# hexapod.net
KiCad netlist of a schematic drawn in EAGLE
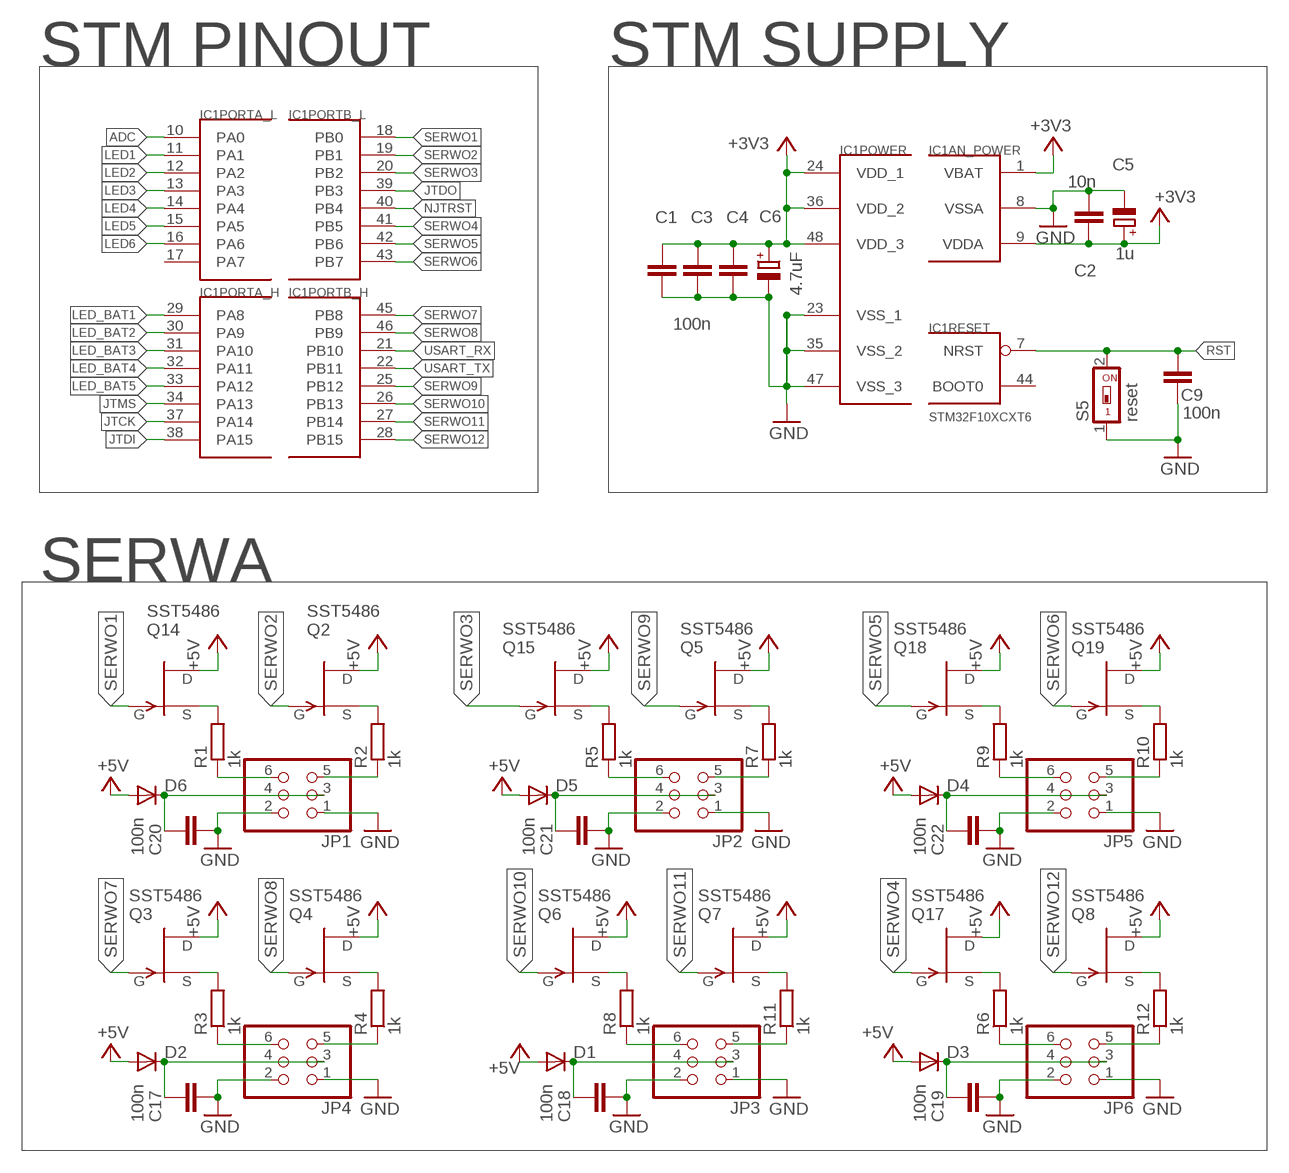
[diagram p0: schematic, sheet 1, part 1 of 2]
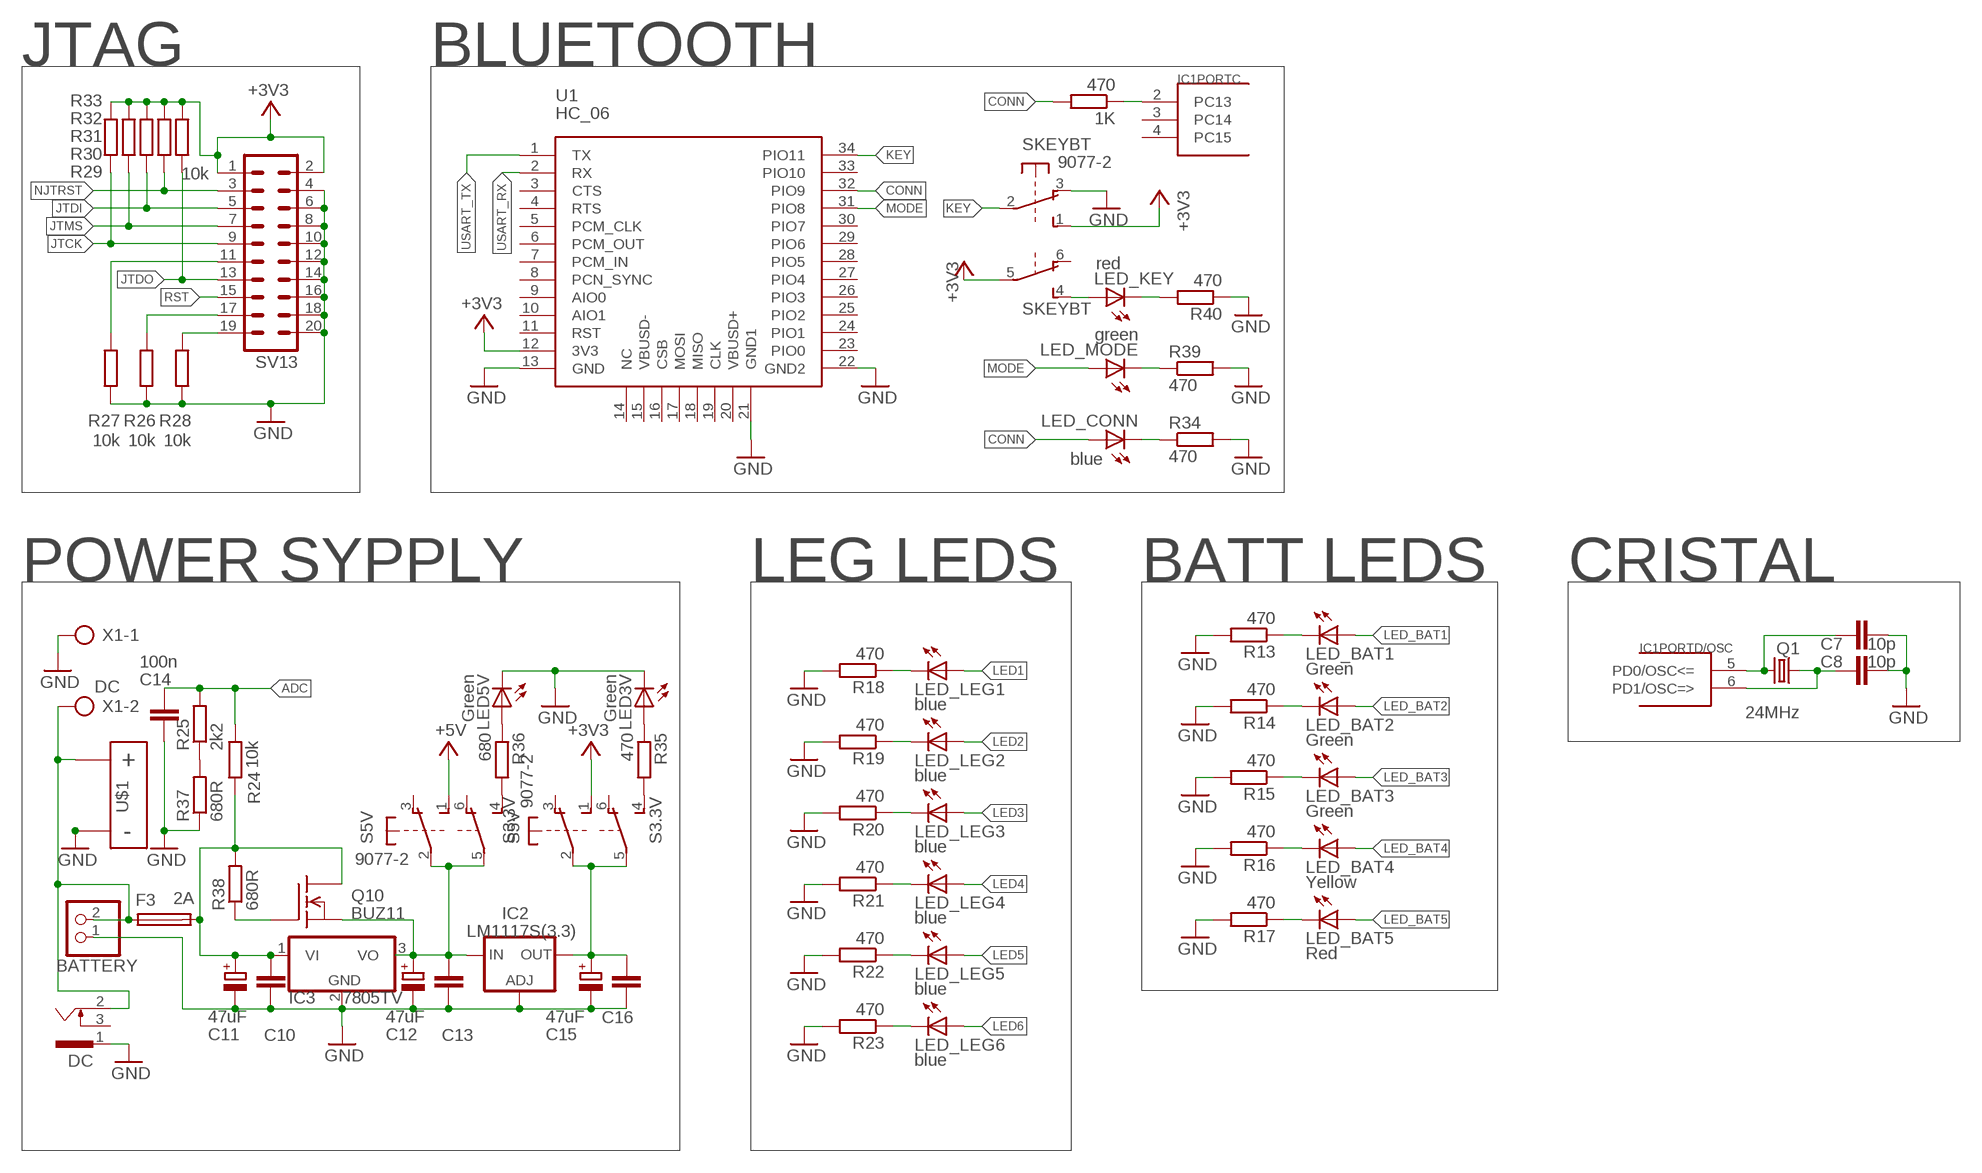
[diagram p1: schematic, sheet 1, part 2 of 2]

(export (version "E")
  (design (tool "Eeschema 10.0.6"))
  (components
    (comp (ref "1K")
      (value "470")
      (footprint "eagle-import:M0805")
      (libsource (lib "eagle-import") (part "R-EU_M0805"))
    )
    (comp (ref "BATTERY")
      (value "PINHD-1X2")
      (footprint "eagle-import:1X02")
      (libsource (lib "eagle-import") (part "PINHD-1X2"))
    )
    (comp (ref "C1")
      (value "100n")
      (footprint "eagle-import:C0805K")
      (libsource (lib "eagle-import") (part "C-EUC0805K"))
    )
    (comp (ref "C2")
      (value "10n")
      (footprint "eagle-import:C0805K")
      (libsource (lib "eagle-import") (part "C-EUC0805K"))
    )
    (comp (ref "C3")
      (value "100n")
      (footprint "eagle-import:C0805K")
      (libsource (lib "eagle-import") (part "C-EUC0805K"))
    )
    (comp (ref "C4")
      (value "100n")
      (footprint "eagle-import:C0805K")
      (libsource (lib "eagle-import") (part "C-EUC0805K"))
    )
    (comp (ref "C5")
      (value "1u")
      (footprint "eagle-import:E2,5-5")
      (libsource (lib "eagle-import") (part "CPOL-EUE2.5-5"))
    )
    (comp (ref "C6")
      (value "4.7uF")
      (footprint "eagle-import:E2,5-5")
      (libsource (lib "eagle-import") (part "CPOL-EUE2.5-5"))
    )
    (comp (ref "C7")
      (value "10p")
      (footprint "eagle-import:C0805K")
      (libsource (lib "eagle-import") (part "C-EUC0805K"))
    )
    (comp (ref "C8")
      (value "10p")
      (footprint "eagle-import:C0805K")
      (libsource (lib "eagle-import") (part "C-EUC0805K"))
    )
    (comp (ref "C9")
      (value "100n")
      (footprint "eagle-import:C0805K")
      (libsource (lib "eagle-import") (part "C-EUC0805K"))
    )
    (comp (ref "C10")
      (value "100n")
      (footprint "eagle-import:C0805K")
      (libsource (lib "eagle-import") (part "C-EUC0805K"))
    )
    (comp (ref "C11")
      (value "47uF")
      (footprint "eagle-import:E2,5-5")
      (libsource (lib "eagle-import") (part "CPOL-EUE2.5-5"))
    )
    (comp (ref "C12")
      (value "47uF")
      (footprint "eagle-import:E2,5-5")
      (libsource (lib "eagle-import") (part "CPOL-EUE2.5-5"))
    )
    (comp (ref "C13")
      (value "100n")
      (footprint "eagle-import:C0805K")
      (libsource (lib "eagle-import") (part "C-EUC0805K"))
    )
    (comp (ref "C14")
      (value "100n")
      (footprint "eagle-import:C0805K")
      (libsource (lib "eagle-import") (part "C-EUC0805K"))
    )
    (comp (ref "C15")
      (value "47uF")
      (footprint "eagle-import:E2,5-5")
      (libsource (lib "eagle-import") (part "CPOL-EUE2.5-5"))
    )
    (comp (ref "C16")
      (value "100n")
      (footprint "eagle-import:C0805K")
      (libsource (lib "eagle-import") (part "C-EUC0805K"))
    )
    (comp (ref "C17")
      (value "100n")
      (footprint "eagle-import:C0805K")
      (libsource (lib "eagle-import") (part "C-EUC0805K"))
    )
    (comp (ref "C18")
      (value "100n")
      (footprint "eagle-import:C0805K")
      (libsource (lib "eagle-import") (part "C-EUC0805K"))
    )
    (comp (ref "C19")
      (value "100n")
      (footprint "eagle-import:C0805K")
      (libsource (lib "eagle-import") (part "C-EUC0805K"))
    )
    (comp (ref "C20")
      (value "100n")
      (footprint "eagle-import:C0805K")
      (libsource (lib "eagle-import") (part "C-EUC0805K"))
    )
    (comp (ref "C21")
      (value "100n")
      (footprint "eagle-import:C0805K")
      (libsource (lib "eagle-import") (part "C-EUC0805K"))
    )
    (comp (ref "C22")
      (value "100n")
      (footprint "eagle-import:C0805K")
      (libsource (lib "eagle-import") (part "C-EUC0805K"))
    )
    (comp (ref "D1")
      (value "DIODE-DO-214AC")
      (footprint "eagle-import:DO-214AC")
      (libsource (lib "eagle-import") (part "DIODE-DO-214AC"))
    )
    (comp (ref "D2")
      (value "DIODE-DO-214AC")
      (footprint "eagle-import:DO-214AC")
      (libsource (lib "eagle-import") (part "DIODE-DO-214AC"))
    )
    (comp (ref "D3")
      (value "DIODE-DO-214AC")
      (footprint "eagle-import:DO-214AC")
      (libsource (lib "eagle-import") (part "DIODE-DO-214AC"))
    )
    (comp (ref "D4")
      (value "DIODE-DO-214AC")
      (footprint "eagle-import:DO-214AC")
      (libsource (lib "eagle-import") (part "DIODE-DO-214AC"))
    )
    (comp (ref "D5")
      (value "DIODE-DO-214AC")
      (footprint "eagle-import:DO-214AC")
      (libsource (lib "eagle-import") (part "DIODE-DO-214AC"))
    )
    (comp (ref "D6")
      (value "DIODE-DO-214AC")
      (footprint "eagle-import:DO-214AC")
      (libsource (lib "eagle-import") (part "DIODE-DO-214AC"))
    )
    (comp (ref "DC")
      (value "733980-62")
      (footprint "eagle-import:733980-62")
      (libsource (lib "eagle-import") (part "73398?0-62"))
    )
    (comp (ref "F3")
      (value "2A")
      (footprint "eagle-import:SH22,5")
      (fields (field (name "MF") "SCHURTER") (field (name "MPN") "0031.8201"))
      (libsource (lib "eagle-import") (part "SH22,5"))
    )
    (comp (ref "IC1")
      (value "STM32F10XCXT6")
      (footprint "eagle-import:TQFP48")
      (libsource (lib "eagle-import") (part "STM32F10XCXT6"))
    )
    (comp (ref "IC2")
      (value "LM1117S(3.3)")
      (footprint "eagle-import:SOT223")
      (libsource (lib "eagle-import") (part "LM317?MSTT3"))
    )
    (comp (ref "IC3")
      (value "7805TV")
      (footprint "eagle-import:TO220V")
      (libsource (lib "eagle-import") (part "78TV05"))
    )
    (comp (ref "JP1")
      (value "PINHD-2X3")
      (footprint "eagle-import:2X03")
      (libsource (lib "eagle-import") (part "PINHD-2X3"))
    )
    (comp (ref "JP2")
      (value "PINHD-2X3")
      (footprint "eagle-import:2X03")
      (libsource (lib "eagle-import") (part "PINHD-2X3"))
    )
    (comp (ref "JP3")
      (value "PINHD-2X3")
      (footprint "eagle-import:2X03")
      (libsource (lib "eagle-import") (part "PINHD-2X3"))
    )
    (comp (ref "JP4")
      (value "PINHD-2X3")
      (footprint "eagle-import:2X03")
      (libsource (lib "eagle-import") (part "PINHD-2X3"))
    )
    (comp (ref "JP5")
      (value "PINHD-2X3")
      (footprint "eagle-import:2X03")
      (libsource (lib "eagle-import") (part "PINHD-2X3"))
    )
    (comp (ref "JP6")
      (value "PINHD-2X3")
      (footprint "eagle-import:2X03")
      (libsource (lib "eagle-import") (part "PINHD-2X3"))
    )
    (comp (ref "LED3V")
      (value "Green")
      (footprint "eagle-import:CHIP-LED0805")
      (libsource (lib "eagle-import") (part "LEDCHIP-LED0805"))
    )
    (comp (ref "LED5V")
      (value "Green")
      (footprint "eagle-import:CHIP-LED0805")
      (libsource (lib "eagle-import") (part "LEDCHIP-LED0805"))
    )
    (comp (ref "LED_BAT1")
      (value "Green")
      (footprint "eagle-import:CHIP-LED0805")
      (libsource (lib "eagle-import") (part "LEDCHIP-LED0805"))
    )
    (comp (ref "LED_BAT2")
      (value "Green")
      (footprint "eagle-import:CHIP-LED0805")
      (libsource (lib "eagle-import") (part "LEDCHIP-LED0805"))
    )
    (comp (ref "LED_BAT3")
      (value "Green")
      (footprint "eagle-import:CHIP-LED0805")
      (libsource (lib "eagle-import") (part "LEDCHIP-LED0805"))
    )
    (comp (ref "LED_BAT4")
      (value "Yellow")
      (footprint "eagle-import:CHIP-LED0805")
      (libsource (lib "eagle-import") (part "LEDCHIP-LED0805"))
    )
    (comp (ref "LED_BAT5")
      (value "Red")
      (footprint "eagle-import:CHIP-LED0805")
      (libsource (lib "eagle-import") (part "LEDCHIP-LED0805"))
    )
    (comp (ref "LED_CONN")
      (value "blue")
      (footprint "eagle-import:CHIP-LED0805")
      (libsource (lib "eagle-import") (part "LEDCHIP-LED0805"))
    )
    (comp (ref "LED_KEY")
      (value "red")
      (footprint "eagle-import:CHIP-LED0805")
      (libsource (lib "eagle-import") (part "LEDCHIP-LED0805"))
    )
    (comp (ref "LED_LEG1")
      (value "blue")
      (footprint "eagle-import:CHIP-LED0805")
      (libsource (lib "eagle-import") (part "LEDCHIP-LED0805"))
    )
    (comp (ref "LED_LEG2")
      (value "blue")
      (footprint "eagle-import:CHIP-LED0805")
      (libsource (lib "eagle-import") (part "LEDCHIP-LED0805"))
    )
    (comp (ref "LED_LEG3")
      (value "blue")
      (footprint "eagle-import:CHIP-LED0805")
      (libsource (lib "eagle-import") (part "LEDCHIP-LED0805"))
    )
    (comp (ref "LED_LEG4")
      (value "blue")
      (footprint "eagle-import:CHIP-LED0805")
      (libsource (lib "eagle-import") (part "LEDCHIP-LED0805"))
    )
    (comp (ref "LED_LEG5")
      (value "blue")
      (footprint "eagle-import:CHIP-LED0805")
      (libsource (lib "eagle-import") (part "LEDCHIP-LED0805"))
    )
    (comp (ref "LED_LEG6")
      (value "blue")
      (footprint "eagle-import:CHIP-LED0805")
      (libsource (lib "eagle-import") (part "LEDCHIP-LED0805"))
    )
    (comp (ref "LED_MODE")
      (value "green")
      (footprint "eagle-import:CHIP-LED0805")
      (libsource (lib "eagle-import") (part "LEDCHIP-LED0805"))
    )
    (comp (ref "Q1")
      (value "24MHz")
      (footprint "eagle-import:SM49")
      (libsource (lib "eagle-import") (part "CRYSTALSM49"))
    )
    (comp (ref "Q2")
      (value "SST5486")
      (footprint "eagle-import:SOT23")
      (libsource (lib "eagle-import") (part "?548SST6"))
    )
    (comp (ref "Q3")
      (value "SST5486")
      (footprint "eagle-import:SOT23")
      (libsource (lib "eagle-import") (part "?548SST6"))
    )
    (comp (ref "Q4")
      (value "SST5486")
      (footprint "eagle-import:SOT23")
      (libsource (lib "eagle-import") (part "?548SST6"))
    )
    (comp (ref "Q5")
      (value "SST5486")
      (footprint "eagle-import:SOT23")
      (libsource (lib "eagle-import") (part "?548SST6"))
    )
    (comp (ref "Q6")
      (value "SST5486")
      (footprint "eagle-import:SOT23")
      (libsource (lib "eagle-import") (part "?548SST6"))
    )
    (comp (ref "Q7")
      (value "SST5486")
      (footprint "eagle-import:SOT23")
      (libsource (lib "eagle-import") (part "?548SST6"))
    )
    (comp (ref "Q8")
      (value "SST5486")
      (footprint "eagle-import:SOT23")
      (libsource (lib "eagle-import") (part "?548SST6"))
    )
    (comp (ref "Q10")
      (value "BUZ11")
      (footprint "eagle-import:TO220")
      (libsource (lib "eagle-import") (part "BUZ11"))
    )
    (comp (ref "Q14")
      (value "SST5486")
      (footprint "eagle-import:SOT23")
      (libsource (lib "eagle-import") (part "?548SST6"))
    )
    (comp (ref "Q15")
      (value "SST5486")
      (footprint "eagle-import:SOT23")
      (libsource (lib "eagle-import") (part "?548SST6"))
    )
    (comp (ref "Q17")
      (value "SST5486")
      (footprint "eagle-import:SOT23")
      (libsource (lib "eagle-import") (part "?548SST6"))
    )
    (comp (ref "Q18")
      (value "SST5486")
      (footprint "eagle-import:SOT23")
      (libsource (lib "eagle-import") (part "?548SST6"))
    )
    (comp (ref "Q19")
      (value "SST5486")
      (footprint "eagle-import:SOT23")
      (libsource (lib "eagle-import") (part "?548SST6"))
    )
    (comp (ref "R1")
      (value "1k")
      (footprint "eagle-import:M0805")
      (libsource (lib "eagle-import") (part "R-EU_M0805"))
    )
    (comp (ref "R2")
      (value "1k")
      (footprint "eagle-import:M0805")
      (libsource (lib "eagle-import") (part "R-EU_M0805"))
    )
    (comp (ref "R3")
      (value "1k")
      (footprint "eagle-import:M0805")
      (libsource (lib "eagle-import") (part "R-EU_M0805"))
    )
    (comp (ref "R4")
      (value "1k")
      (footprint "eagle-import:M0805")
      (libsource (lib "eagle-import") (part "R-EU_M0805"))
    )
    (comp (ref "R5")
      (value "1k")
      (footprint "eagle-import:M0805")
      (libsource (lib "eagle-import") (part "R-EU_M0805"))
    )
    (comp (ref "R6")
      (value "1k")
      (footprint "eagle-import:M0805")
      (libsource (lib "eagle-import") (part "R-EU_M0805"))
    )
    (comp (ref "R7")
      (value "1k")
      (footprint "eagle-import:M0805")
      (libsource (lib "eagle-import") (part "R-EU_M0805"))
    )
    (comp (ref "R8")
      (value "1k")
      (footprint "eagle-import:M0805")
      (libsource (lib "eagle-import") (part "R-EU_M0805"))
    )
    (comp (ref "R9")
      (value "1k")
      (footprint "eagle-import:M0805")
      (libsource (lib "eagle-import") (part "R-EU_M0805"))
    )
    (comp (ref "R10")
      (value "1k")
      (footprint "eagle-import:M0805")
      (libsource (lib "eagle-import") (part "R-EU_M0805"))
    )
    (comp (ref "R11")
      (value "1k")
      (footprint "eagle-import:M0805")
      (libsource (lib "eagle-import") (part "R-EU_M0805"))
    )
    (comp (ref "R12")
      (value "1k")
      (footprint "eagle-import:M0805")
      (libsource (lib "eagle-import") (part "R-EU_M0805"))
    )
    (comp (ref "R13")
      (value "470")
      (footprint "eagle-import:M0805")
      (libsource (lib "eagle-import") (part "R-EU_M0805"))
    )
    (comp (ref "R14")
      (value "470")
      (footprint "eagle-import:M0805")
      (libsource (lib "eagle-import") (part "R-EU_M0805"))
    )
    (comp (ref "R15")
      (value "470")
      (footprint "eagle-import:M0805")
      (libsource (lib "eagle-import") (part "R-EU_M0805"))
    )
    (comp (ref "R16")
      (value "470")
      (footprint "eagle-import:M0805")
      (libsource (lib "eagle-import") (part "R-EU_M0805"))
    )
    (comp (ref "R17")
      (value "470")
      (footprint "eagle-import:M0805")
      (libsource (lib "eagle-import") (part "R-EU_M0805"))
    )
    (comp (ref "R18")
      (value "470")
      (footprint "eagle-import:M0805")
      (libsource (lib "eagle-import") (part "R-EU_M0805"))
    )
    (comp (ref "R19")
      (value "470")
      (footprint "eagle-import:M0805")
      (libsource (lib "eagle-import") (part "R-EU_M0805"))
    )
    (comp (ref "R20")
      (value "470")
      (footprint "eagle-import:M0805")
      (libsource (lib "eagle-import") (part "R-EU_M0805"))
    )
    (comp (ref "R21")
      (value "470")
      (footprint "eagle-import:M0805")
      (libsource (lib "eagle-import") (part "R-EU_M0805"))
    )
    (comp (ref "R22")
      (value "470")
      (footprint "eagle-import:M0805")
      (libsource (lib "eagle-import") (part "R-EU_M0805"))
    )
    (comp (ref "R23")
      (value "470")
      (footprint "eagle-import:M0805")
      (libsource (lib "eagle-import") (part "R-EU_M0805"))
    )
    (comp (ref "R24")
      (value "10k")
      (footprint "eagle-import:M0805")
      (libsource (lib "eagle-import") (part "R-EU_M0805"))
    )
    (comp (ref "R25")
      (value "2k2")
      (footprint "eagle-import:M0805")
      (libsource (lib "eagle-import") (part "R-EU_M0805"))
    )
    (comp (ref "R26")
      (value "10k")
      (footprint "eagle-import:M0805")
      (libsource (lib "eagle-import") (part "R-EU_M0805"))
    )
    (comp (ref "R27")
      (value "10k")
      (footprint "eagle-import:M0805")
      (libsource (lib "eagle-import") (part "R-EU_M0805"))
    )
    (comp (ref "R28")
      (value "10k")
      (footprint "eagle-import:M0805")
      (libsource (lib "eagle-import") (part "R-EU_M0805"))
    )
    (comp (ref "R29")
      (value "10k")
      (footprint "eagle-import:M0805")
      (libsource (lib "eagle-import") (part "R-EU_M0805"))
    )
    (comp (ref "R30")
      (value "10k")
      (footprint "eagle-import:M0805")
      (libsource (lib "eagle-import") (part "R-EU_M0805"))
    )
    (comp (ref "R31")
      (value "10k")
      (footprint "eagle-import:M0805")
      (libsource (lib "eagle-import") (part "R-EU_M0805"))
    )
    (comp (ref "R32")
      (value "10k")
      (footprint "eagle-import:M0805")
      (libsource (lib "eagle-import") (part "R-EU_M0805"))
    )
    (comp (ref "R33")
      (value "10k")
      (footprint "eagle-import:M0805")
      (libsource (lib "eagle-import") (part "R-EU_M0805"))
    )
    (comp (ref "R34")
      (value "470")
      (footprint "eagle-import:M0805")
      (libsource (lib "eagle-import") (part "R-EU_M0805"))
    )
    (comp (ref "R35")
      (value "470")
      (footprint "eagle-import:M0805")
      (libsource (lib "eagle-import") (part "R-EU_M0805"))
    )
    (comp (ref "R36")
      (value "680")
      (footprint "eagle-import:M0805")
      (libsource (lib "eagle-import") (part "R-EU_M0805"))
    )
    (comp (ref "R37")
      (value "680R")
      (footprint "eagle-import:M0805")
      (libsource (lib "eagle-import") (part "R-EU_M0805"))
    )
    (comp (ref "R38")
      (value "680R")
      (footprint "eagle-import:M0805")
      (libsource (lib "eagle-import") (part "R-EU_M0805"))
    )
    (comp (ref "R39")
      (value "470")
      (footprint "eagle-import:M0805")
      (libsource (lib "eagle-import") (part "R-EU_M0805"))
    )
    (comp (ref "R40")
      (value "470")
      (footprint "eagle-import:M0805")
      (libsource (lib "eagle-import") (part "R-EU_M0805"))
    )
    (comp (ref "S3.3V")
      (value "9077-2")
      (footprint "eagle-import:9077-2")
      (libsource (lib "eagle-import") (part "9077-2"))
    )
    (comp (ref "S5")
      (value "reset")
      (footprint "eagle-import:SMS-001")
      (libsource (lib "eagle-import") (part "SWS001"))
    )
    (comp (ref "S5V")
      (value "9077-2")
      (footprint "eagle-import:9077-2")
      (libsource (lib "eagle-import") (part "9077-2"))
    )
    (comp (ref "SKEYBT")
      (value "9077-2")
      (footprint "eagle-import:9077-2")
      (libsource (lib "eagle-import") (part "9077-2"))
    )
    (comp (ref "SV13")
      (value "ML20")
      (footprint "eagle-import:ML20")
      (libsource (lib "eagle-import") (part "ML20"))
    )
    (comp (ref "U$1")
      (value "DEANS.MALE")
      (footprint "eagle-import:DEANSM")
      (libsource (lib "eagle-import") (part "DEANS.MALE"))
    )
    (comp (ref "U1")
      (value "HC_06")
      (footprint "eagle-import:BLUETOOTH_SMD")
      (libsource (lib "eagle-import") (part "HC_05"))
    )
    (comp (ref "X1")
      (value "DC")
      (footprint "eagle-import:AK500_2")
      (libsource (lib "eagle-import") (part "AK500/2"))
    )
  )
  (nets
    (net (code "1") (name "+3V3") (class "Default")
      (node (ref "C1") (pin "1") (pinfunction "1_1") (pintype "passive"))
      (node (ref "C2") (pin "1") (pinfunction "1_1") (pintype "passive"))
      (node (ref "C3") (pin "1") (pinfunction "1_1") (pintype "passive"))
      (node (ref "C4") (pin "1") (pinfunction "1_1") (pintype "passive"))
      (node (ref "C5") (pin "+") (pinfunction "+_+") (pintype "passive"))
      (node (ref "C6") (pin "+") (pinfunction "+_+") (pintype "passive"))
      (node (ref "IC1") (pin "1") (pinfunction "VBAT_1") (pintype "power_in"))
      (node (ref "IC1") (pin "24") (pinfunction "VDD_1_24") (pintype "power_in"))
      (node (ref "IC1") (pin "36") (pinfunction "VDD_2_36") (pintype "power_in"))
      (node (ref "IC1") (pin "48") (pinfunction "VDD_3_48") (pintype "power_in"))
      (node (ref "IC1") (pin "9") (pinfunction "VDDA_9") (pintype "power_in"))
      (node (ref "R29") (pin "2") (pinfunction "2_2") (pintype "passive"))
      (node (ref "R30") (pin "2") (pinfunction "2_2") (pintype "passive"))
      (node (ref "R31") (pin "2") (pinfunction "2_2") (pintype "passive"))
      (node (ref "R32") (pin "2") (pinfunction "2_2") (pintype "passive"))
      (node (ref "R33") (pin "2") (pinfunction "2_2") (pintype "passive"))
      (node (ref "S3.3V") (pin "1") (pinfunction "S_1") (pintype "passive"))
      (node (ref "SKEYBT") (pin "1") (pinfunction "S_1") (pintype "passive"))
      (node (ref "SKEYBT") (pin "5") (pinfunction "P_5") (pintype "passive"))
      (node (ref "SV13") (pin "1") (pinfunction "1_1") (pintype "passive"))
      (node (ref "SV13") (pin "2") (pinfunction "2_2") (pintype "passive"))
      (node (ref "U1") (pin "12") (pinfunction "3V3_12") (pintype "bidirectional"))
    )
    (net (code "2") (name "+5V") (class "Default")
      (node (ref "D1") (pin "A") (pinfunction "A_A") (pintype "passive"))
      (node (ref "D2") (pin "A") (pinfunction "A_A") (pintype "passive"))
      (node (ref "D3") (pin "A") (pinfunction "A_A") (pintype "passive"))
      (node (ref "D4") (pin "A") (pinfunction "A_A") (pintype "passive"))
      (node (ref "D5") (pin "A") (pinfunction "A_A") (pintype "passive"))
      (node (ref "D6") (pin "A") (pinfunction "A_A") (pintype "passive"))
      (node (ref "Q14") (pin "1") (pinfunction "D_1") (pintype "passive"))
      (node (ref "Q15") (pin "1") (pinfunction "D_1") (pintype "passive"))
      (node (ref "Q17") (pin "1") (pinfunction "D_1") (pintype "passive"))
      (node (ref "Q18") (pin "1") (pinfunction "D_1") (pintype "passive"))
      (node (ref "Q19") (pin "1") (pinfunction "D_1") (pintype "passive"))
      (node (ref "Q2") (pin "1") (pinfunction "D_1") (pintype "passive"))
      (node (ref "Q3") (pin "1") (pinfunction "D_1") (pintype "passive"))
      (node (ref "Q4") (pin "1") (pinfunction "D_1") (pintype "passive"))
      (node (ref "Q5") (pin "1") (pinfunction "D_1") (pintype "passive"))
      (node (ref "Q6") (pin "1") (pinfunction "D_1") (pintype "passive"))
      (node (ref "Q7") (pin "1") (pinfunction "D_1") (pintype "passive"))
      (node (ref "Q8") (pin "1") (pinfunction "D_1") (pintype "passive"))
      (node (ref "S5V") (pin "1") (pinfunction "S_1") (pintype "passive"))
    )
    (net (code "3") (name "ADC") (class "Default")
      (node (ref "C14") (pin "1") (pinfunction "1_1") (pintype "passive"))
      (node (ref "IC1") (pin "10") (pinfunction "PA0_10") (pintype "bidirectional"))
      (node (ref "R24") (pin "1") (pinfunction "1_1") (pintype "passive"))
      (node (ref "R25") (pin "2") (pinfunction "2_2") (pintype "passive"))
    )
    (net (code "4") (name "CONN") (class "Default")
      (node (ref "1K") (pin "2") (pinfunction "2_2") (pintype "passive"))
      (node (ref "LED_CONN") (pin "A") (pinfunction "A_A") (pintype "passive"))
      (node (ref "U1") (pin "32") (pinfunction "PIO9_32") (pintype "bidirectional"))
    )
    (net (code "5") (name "GND") (class "Default")
      (node (ref "BATTERY") (pin "1") (pinfunction "1_1") (pintype "passive"))
      (node (ref "C1") (pin "2") (pinfunction "2_2") (pintype "passive"))
      (node (ref "C10") (pin "2") (pinfunction "2_2") (pintype "passive"))
      (node (ref "C11") (pin "-") (pinfunction "-_-") (pintype "passive"))
      (node (ref "C12") (pin "-") (pinfunction "-_-") (pintype "passive"))
      (node (ref "C13") (pin "2") (pinfunction "2_2") (pintype "passive"))
      (node (ref "C14") (pin "2") (pinfunction "2_2") (pintype "passive"))
      (node (ref "C15") (pin "-") (pinfunction "-_-") (pintype "passive"))
      (node (ref "C16") (pin "2") (pinfunction "2_2") (pintype "passive"))
      (node (ref "C17") (pin "2") (pinfunction "2_2") (pintype "passive"))
      (node (ref "C18") (pin "2") (pinfunction "2_2") (pintype "passive"))
      (node (ref "C19") (pin "2") (pinfunction "2_2") (pintype "passive"))
      (node (ref "C2") (pin "2") (pinfunction "2_2") (pintype "passive"))
      (node (ref "C20") (pin "2") (pinfunction "2_2") (pintype "passive"))
      (node (ref "C21") (pin "2") (pinfunction "2_2") (pintype "passive"))
      (node (ref "C22") (pin "2") (pinfunction "2_2") (pintype "passive"))
      (node (ref "C3") (pin "2") (pinfunction "2_2") (pintype "passive"))
      (node (ref "C4") (pin "2") (pinfunction "2_2") (pintype "passive"))
      (node (ref "C5") (pin "-") (pinfunction "-_-") (pintype "passive"))
      (node (ref "C6") (pin "-") (pinfunction "-_-") (pintype "passive"))
      (node (ref "C7") (pin "2") (pinfunction "2_2") (pintype "passive"))
      (node (ref "C8") (pin "2") (pinfunction "2_2") (pintype "passive"))
      (node (ref "C9") (pin "1") (pinfunction "1_1") (pintype "passive"))
      (node (ref "DC") (pin "1") (pinfunction "1_1") (pintype "passive"))
      (node (ref "IC1") (pin "23") (pinfunction "VSS_1_23") (pintype "power_in"))
      (node (ref "IC1") (pin "35") (pinfunction "VSS_2_35") (pintype "power_in"))
      (node (ref "IC1") (pin "47") (pinfunction "VSS_3_47") (pintype "power_in"))
      (node (ref "IC1") (pin "8") (pinfunction "VSSA_8") (pintype "power_in"))
      (node (ref "IC2") (pin "1") (pinfunction "ADJ_1") (pintype "input"))
      (node (ref "IC3") (pin "2") (pinfunction "GND_2") (pintype "passive"))
      (node (ref "JP1") (pin "1") (pinfunction "1_1") (pintype "passive"))
      (node (ref "JP1") (pin "2") (pinfunction "2_2") (pintype "passive"))
      (node (ref "JP2") (pin "1") (pinfunction "1_1") (pintype "passive"))
      (node (ref "JP2") (pin "2") (pinfunction "2_2") (pintype "passive"))
      (node (ref "JP3") (pin "1") (pinfunction "1_1") (pintype "passive"))
      (node (ref "JP3") (pin "2") (pinfunction "2_2") (pintype "passive"))
      (node (ref "JP4") (pin "1") (pinfunction "1_1") (pintype "passive"))
      (node (ref "JP4") (pin "2") (pinfunction "2_2") (pintype "passive"))
      (node (ref "JP5") (pin "1") (pinfunction "1_1") (pintype "passive"))
      (node (ref "JP5") (pin "2") (pinfunction "2_2") (pintype "passive"))
      (node (ref "JP6") (pin "1") (pinfunction "1_1") (pintype "passive"))
      (node (ref "JP6") (pin "2") (pinfunction "2_2") (pintype "passive"))
      (node (ref "LED3V") (pin "C") (pinfunction "C_C") (pintype "passive"))
      (node (ref "LED5V") (pin "C") (pinfunction "C_C") (pintype "passive"))
      (node (ref "R13") (pin "2") (pinfunction "2_2") (pintype "passive"))
      (node (ref "R14") (pin "2") (pinfunction "2_2") (pintype "passive"))
      (node (ref "R15") (pin "2") (pinfunction "2_2") (pintype "passive"))
      (node (ref "R16") (pin "2") (pinfunction "2_2") (pintype "passive"))
      (node (ref "R17") (pin "2") (pinfunction "2_2") (pintype "passive"))
      (node (ref "R18") (pin "2") (pinfunction "2_2") (pintype "passive"))
      (node (ref "R19") (pin "2") (pinfunction "2_2") (pintype "passive"))
      (node (ref "R20") (pin "2") (pinfunction "2_2") (pintype "passive"))
      (node (ref "R21") (pin "2") (pinfunction "2_2") (pintype "passive"))
      (node (ref "R22") (pin "2") (pinfunction "2_2") (pintype "passive"))
      (node (ref "R23") (pin "2") (pinfunction "2_2") (pintype "passive"))
      (node (ref "R26") (pin "1") (pinfunction "1_1") (pintype "passive"))
      (node (ref "R27") (pin "1") (pinfunction "1_1") (pintype "passive"))
      (node (ref "R28") (pin "1") (pinfunction "1_1") (pintype "passive"))
      (node (ref "R34") (pin "2") (pinfunction "2_2") (pintype "passive"))
      (node (ref "R37") (pin "1") (pinfunction "1_1") (pintype "passive"))
      (node (ref "R39") (pin "2") (pinfunction "2_2") (pintype "passive"))
      (node (ref "R40") (pin "1") (pinfunction "1_1") (pintype "passive"))
      (node (ref "S5") (pin "1") (pinfunction "1_1") (pintype "passive"))
      (node (ref "SKEYBT") (pin "3") (pinfunction "O_3") (pintype "passive"))
      (node (ref "SV13") (pin "10") (pinfunction "10_10") (pintype "passive"))
      (node (ref "SV13") (pin "12") (pinfunction "12_12") (pintype "passive"))
      (node (ref "SV13") (pin "14") (pinfunction "14_14") (pintype "passive"))
      (node (ref "SV13") (pin "16") (pinfunction "16_16") (pintype "passive"))
      (node (ref "SV13") (pin "18") (pinfunction "18_18") (pintype "passive"))
      (node (ref "SV13") (pin "20") (pinfunction "20_20") (pintype "passive"))
      (node (ref "SV13") (pin "4") (pinfunction "4_4") (pintype "passive"))
      (node (ref "SV13") (pin "6") (pinfunction "6_6") (pintype "passive"))
      (node (ref "SV13") (pin "8") (pinfunction "8_8") (pintype "passive"))
      (node (ref "U$1") (pin "P$NEG") (pinfunction "P$NEG_P$NEG") (pintype "bidirectional"))
      (node (ref "U1") (pin "13") (pinfunction "GND_13") (pintype "bidirectional"))
      (node (ref "U1") (pin "21") (pinfunction "GND1_21") (pintype "bidirectional"))
      (node (ref "U1") (pin "22") (pinfunction "GND2_22") (pintype "bidirectional"))
      (node (ref "X1") (pin "1") (pinfunction "KL_1") (pintype "passive"))
    )
    (net (code "6") (name "JTCK") (class "Default")
      (node (ref "IC1") (pin "37") (pinfunction "PA14_37") (pintype "bidirectional"))
      (node (ref "R29") (pin "1") (pinfunction "1_1") (pintype "passive"))
      (node (ref "SV13") (pin "9") (pinfunction "9_9") (pintype "passive"))
    )
    (net (code "7") (name "JTDI") (class "Default")
      (node (ref "IC1") (pin "38") (pinfunction "PA15_38") (pintype "bidirectional"))
      (node (ref "R31") (pin "1") (pinfunction "1_1") (pintype "passive"))
      (node (ref "SV13") (pin "5") (pinfunction "5_5") (pintype "passive"))
    )
    (net (code "8") (name "JTDO") (class "Default")
      (node (ref "IC1") (pin "39") (pinfunction "PB3_39") (pintype "bidirectional"))
      (node (ref "R33") (pin "1") (pinfunction "1_1") (pintype "passive"))
      (node (ref "SV13") (pin "13") (pinfunction "13_13") (pintype "passive"))
    )
    (net (code "9") (name "JTMS") (class "Default")
      (node (ref "IC1") (pin "34") (pinfunction "PA13_34") (pintype "bidirectional"))
      (node (ref "R30") (pin "1") (pinfunction "1_1") (pintype "passive"))
      (node (ref "SV13") (pin "7") (pinfunction "7_7") (pintype "passive"))
    )
    (net (code "10") (name "KEY") (class "Default")
      (node (ref "SKEYBT") (pin "2") (pinfunction "P_2") (pintype "passive"))
      (node (ref "U1") (pin "34") (pinfunction "PIO11_34") (pintype "bidirectional"))
    )
    (net (code "11") (name "LED1") (class "Default")
      (node (ref "IC1") (pin "11") (pinfunction "PA1_11") (pintype "bidirectional"))
      (node (ref "LED_LEG1") (pin "A") (pinfunction "A_A") (pintype "passive"))
    )
    (net (code "12") (name "LED2") (class "Default")
      (node (ref "IC1") (pin "12") (pinfunction "PA2_12") (pintype "bidirectional"))
      (node (ref "LED_LEG2") (pin "A") (pinfunction "A_A") (pintype "passive"))
    )
    (net (code "13") (name "LED3") (class "Default")
      (node (ref "IC1") (pin "13") (pinfunction "PA3_13") (pintype "bidirectional"))
      (node (ref "LED_LEG3") (pin "A") (pinfunction "A_A") (pintype "passive"))
    )
    (net (code "14") (name "LED4") (class "Default")
      (node (ref "IC1") (pin "14") (pinfunction "PA4_14") (pintype "bidirectional"))
      (node (ref "LED_LEG4") (pin "A") (pinfunction "A_A") (pintype "passive"))
    )
    (net (code "15") (name "LED5") (class "Default")
      (node (ref "IC1") (pin "15") (pinfunction "PA5_15") (pintype "bidirectional"))
      (node (ref "LED_LEG5") (pin "A") (pinfunction "A_A") (pintype "passive"))
    )
    (net (code "16") (name "LED6") (class "Default")
      (node (ref "IC1") (pin "16") (pinfunction "PA6_16") (pintype "bidirectional"))
      (node (ref "LED_LEG6") (pin "A") (pinfunction "A_A") (pintype "passive"))
    )
    (net (code "17") (name "LED_BAT1") (class "Default")
      (node (ref "IC1") (pin "29") (pinfunction "PA8_29") (pintype "bidirectional"))
      (node (ref "LED_BAT1") (pin "A") (pinfunction "A_A") (pintype "passive"))
    )
    (net (code "18") (name "LED_BAT2") (class "Default")
      (node (ref "IC1") (pin "30") (pinfunction "PA9_30") (pintype "bidirectional"))
      (node (ref "LED_BAT2") (pin "A") (pinfunction "A_A") (pintype "passive"))
    )
    (net (code "19") (name "LED_BAT3") (class "Default")
      (node (ref "IC1") (pin "31") (pinfunction "PA10_31") (pintype "bidirectional"))
      (node (ref "LED_BAT3") (pin "A") (pinfunction "A_A") (pintype "passive"))
    )
    (net (code "20") (name "LED_BAT4") (class "Default")
      (node (ref "IC1") (pin "32") (pinfunction "PA11_32") (pintype "bidirectional"))
      (node (ref "LED_BAT4") (pin "A") (pinfunction "A_A") (pintype "passive"))
    )
    (net (code "21") (name "LED_BAT5") (class "Default")
      (node (ref "IC1") (pin "33") (pinfunction "PA12_33") (pintype "bidirectional"))
      (node (ref "LED_BAT5") (pin "A") (pinfunction "A_A") (pintype "passive"))
    )
    (net (code "22") (name "MODE") (class "Default")
      (node (ref "LED_MODE") (pin "A") (pinfunction "A_A") (pintype "passive"))
      (node (ref "U1") (pin "31") (pinfunction "PIO8_31") (pintype "bidirectional"))
    )
    (net (code "23") (name "NJTRST") (class "Default")
      (node (ref "IC1") (pin "40") (pinfunction "PB4_40") (pintype "bidirectional"))
      (node (ref "R32") (pin "1") (pinfunction "1_1") (pintype "passive"))
      (node (ref "SV13") (pin "3") (pinfunction "3_3") (pintype "passive"))
    )
    (net (code "24") (name "Net-(C17-Pad1)") (class "Default")
      (node (ref "C17") (pin "1") (pinfunction "1_1") (pintype "passive"))
      (node (ref "D2") (pin "C") (pinfunction "C_C") (pintype "passive"))
      (node (ref "JP4") (pin "3") (pinfunction "3_3") (pintype "passive"))
      (node (ref "JP4") (pin "4") (pinfunction "4_4") (pintype "passive"))
    )
    (net (code "25") (name "Net-(C18-Pad1)") (class "Default")
      (node (ref "C18") (pin "1") (pinfunction "1_1") (pintype "passive"))
      (node (ref "D1") (pin "C") (pinfunction "C_C") (pintype "passive"))
      (node (ref "JP3") (pin "3") (pinfunction "3_3") (pintype "passive"))
      (node (ref "JP3") (pin "4") (pinfunction "4_4") (pintype "passive"))
    )
    (net (code "26") (name "Net-(C19-Pad1)") (class "Default")
      (node (ref "C19") (pin "1") (pinfunction "1_1") (pintype "passive"))
      (node (ref "D3") (pin "C") (pinfunction "C_C") (pintype "passive"))
      (node (ref "JP6") (pin "3") (pinfunction "3_3") (pintype "passive"))
      (node (ref "JP6") (pin "4") (pinfunction "4_4") (pintype "passive"))
    )
    (net (code "27") (name "Net-(C20-Pad1)") (class "Default")
      (node (ref "C20") (pin "1") (pinfunction "1_1") (pintype "passive"))
      (node (ref "D6") (pin "C") (pinfunction "C_C") (pintype "passive"))
      (node (ref "JP1") (pin "3") (pinfunction "3_3") (pintype "passive"))
      (node (ref "JP1") (pin "4") (pinfunction "4_4") (pintype "passive"))
    )
    (net (code "28") (name "Net-(C21-Pad1)") (class "Default")
      (node (ref "C21") (pin "1") (pinfunction "1_1") (pintype "passive"))
      (node (ref "D5") (pin "C") (pinfunction "C_C") (pintype "passive"))
      (node (ref "JP2") (pin "3") (pinfunction "3_3") (pintype "passive"))
      (node (ref "JP2") (pin "4") (pinfunction "4_4") (pintype "passive"))
    )
    (net (code "29") (name "Net-(C22-Pad1)") (class "Default")
      (node (ref "C22") (pin "1") (pinfunction "1_1") (pintype "passive"))
      (node (ref "D4") (pin "C") (pinfunction "C_C") (pintype "passive"))
      (node (ref "JP5") (pin "3") (pinfunction "3_3") (pintype "passive"))
      (node (ref "JP5") (pin "4") (pinfunction "4_4") (pintype "passive"))
    )
    (net (code "30") (name "Net-(IC1F-PC13)") (class "Default")
      (node (ref "1K") (pin "1") (pinfunction "1_1") (pintype "passive"))
      (node (ref "IC1") (pin "2") (pinfunction "PC13_2") (pintype "bidirectional"))
    )
    (net (code "31") (name "Net-(IC1G-PD0{slash}OSC<=)") (class "Default")
      (node (ref "C7") (pin "1") (pinfunction "1_1") (pintype "passive"))
      (node (ref "IC1") (pin "5") (pinfunction "PD0/OSC<=_5") (pintype "bidirectional"))
      (node (ref "Q1") (pin "2") (pinfunction "2_2") (pintype "passive"))
    )
    (net (code "32") (name "Net-(IC1G-PD1{slash}OSC=>)") (class "Default")
      (node (ref "C8") (pin "1") (pinfunction "1_1") (pintype "passive"))
      (node (ref "IC1") (pin "6") (pinfunction "PD1/OSC=>_6") (pintype "bidirectional"))
      (node (ref "Q1") (pin "1") (pinfunction "1_1") (pintype "passive"))
    )
    (net (code "33") (name "Net-(IC2-IN)") (class "Default")
      (node (ref "C12") (pin "+") (pinfunction "+_+") (pintype "passive"))
      (node (ref "C13") (pin "1") (pinfunction "1_1") (pintype "passive"))
      (node (ref "IC2") (pin "3") (pinfunction "IN_3") (pintype "input"))
      (node (ref "IC3") (pin "3") (pinfunction "VO_3") (pintype "passive"))
      (node (ref "Q10") (pin "3") (pinfunction "S_3") (pintype "passive"))
      (node (ref "S5V") (pin "2") (pinfunction "P_2") (pintype "passive"))
      (node (ref "S5V") (pin "5") (pinfunction "P_5") (pintype "passive"))
    )
    (net (code "34") (name "Net-(IC2-OUT)") (class "Default")
      (node (ref "C15") (pin "+") (pinfunction "+_+") (pintype "passive"))
      (node (ref "C16") (pin "1") (pinfunction "1_1") (pintype "passive"))
      (node (ref "IC2") (pin "4") (pinfunction "OUT_4") (pintype "passive"))
      (node (ref "S3.3V") (pin "2") (pinfunction "P_2") (pintype "passive"))
      (node (ref "S3.3V") (pin "5") (pinfunction "P_5") (pintype "passive"))
    )
    (net (code "35") (name "Net-(IC3-VI)") (class "Default")
      (node (ref "C10") (pin "1") (pinfunction "1_1") (pintype "passive"))
      (node (ref "C11") (pin "+") (pinfunction "+_+") (pintype "passive"))
      (node (ref "F3") (pin "2") (pinfunction "2_2") (pintype "passive"))
      (node (ref "IC3") (pin "1") (pinfunction "VI_1") (pintype "input"))
      (node (ref "Q10") (pin "2") (pinfunction "D_2") (pintype "passive"))
      (node (ref "R24") (pin "2") (pinfunction "2_2") (pintype "passive"))
      (node (ref "R38") (pin "2") (pinfunction "2_2") (pintype "passive"))
    )
    (net (code "36") (name "Net-(JP1-Pad5)") (class "Default")
      (node (ref "JP1") (pin "5") (pinfunction "5_5") (pintype "passive"))
      (node (ref "R2") (pin "1") (pinfunction "1_1") (pintype "passive"))
    )
    (net (code "37") (name "Net-(JP1-Pad6)") (class "Default")
      (node (ref "JP1") (pin "6") (pinfunction "6_6") (pintype "passive"))
      (node (ref "R1") (pin "1") (pinfunction "1_1") (pintype "passive"))
    )
    (net (code "38") (name "Net-(JP2-Pad5)") (class "Default")
      (node (ref "JP2") (pin "5") (pinfunction "5_5") (pintype "passive"))
      (node (ref "R7") (pin "1") (pinfunction "1_1") (pintype "passive"))
    )
    (net (code "39") (name "Net-(JP2-Pad6)") (class "Default")
      (node (ref "JP2") (pin "6") (pinfunction "6_6") (pintype "passive"))
      (node (ref "R5") (pin "1") (pinfunction "1_1") (pintype "passive"))
    )
    (net (code "40") (name "Net-(JP3-Pad5)") (class "Default")
      (node (ref "JP3") (pin "5") (pinfunction "5_5") (pintype "passive"))
      (node (ref "R11") (pin "1") (pinfunction "1_1") (pintype "passive"))
    )
    (net (code "41") (name "Net-(JP3-Pad6)") (class "Default")
      (node (ref "JP3") (pin "6") (pinfunction "6_6") (pintype "passive"))
      (node (ref "R8") (pin "1") (pinfunction "1_1") (pintype "passive"))
    )
    (net (code "42") (name "Net-(JP4-Pad5)") (class "Default")
      (node (ref "JP4") (pin "5") (pinfunction "5_5") (pintype "passive"))
      (node (ref "R4") (pin "1") (pinfunction "1_1") (pintype "passive"))
    )
    (net (code "43") (name "Net-(JP4-Pad6)") (class "Default")
      (node (ref "JP4") (pin "6") (pinfunction "6_6") (pintype "passive"))
      (node (ref "R3") (pin "1") (pinfunction "1_1") (pintype "passive"))
    )
    (net (code "44") (name "Net-(JP5-Pad5)") (class "Default")
      (node (ref "JP5") (pin "5") (pinfunction "5_5") (pintype "passive"))
      (node (ref "R10") (pin "1") (pinfunction "1_1") (pintype "passive"))
    )
    (net (code "45") (name "Net-(JP5-Pad6)") (class "Default")
      (node (ref "JP5") (pin "6") (pinfunction "6_6") (pintype "passive"))
      (node (ref "R9") (pin "1") (pinfunction "1_1") (pintype "passive"))
    )
    (net (code "46") (name "Net-(JP6-Pad5)") (class "Default")
      (node (ref "JP6") (pin "5") (pinfunction "5_5") (pintype "passive"))
      (node (ref "R12") (pin "1") (pinfunction "1_1") (pintype "passive"))
    )
    (net (code "47") (name "Net-(JP6-Pad6)") (class "Default")
      (node (ref "JP6") (pin "6") (pinfunction "6_6") (pintype "passive"))
      (node (ref "R6") (pin "1") (pinfunction "1_1") (pintype "passive"))
    )
    (net (code "48") (name "Net-(LED3V-PadA)") (class "Default")
      (node (ref "LED3V") (pin "A") (pinfunction "A_A") (pintype "passive"))
      (node (ref "R35") (pin "1") (pinfunction "1_1") (pintype "passive"))
    )
    (net (code "49") (name "Net-(LED5V-PadA)") (class "Default")
      (node (ref "LED5V") (pin "A") (pinfunction "A_A") (pintype "passive"))
      (node (ref "R36") (pin "1") (pinfunction "1_1") (pintype "passive"))
    )
    (net (code "50") (name "Net-(LED_BAT1-PadC)") (class "Default")
      (node (ref "LED_BAT1") (pin "C") (pinfunction "C_C") (pintype "passive"))
      (node (ref "R13") (pin "1") (pinfunction "1_1") (pintype "passive"))
    )
    (net (code "51") (name "Net-(LED_BAT2-PadC)") (class "Default")
      (node (ref "LED_BAT2") (pin "C") (pinfunction "C_C") (pintype "passive"))
      (node (ref "R14") (pin "1") (pinfunction "1_1") (pintype "passive"))
    )
    (net (code "52") (name "Net-(LED_BAT3-PadC)") (class "Default")
      (node (ref "LED_BAT3") (pin "C") (pinfunction "C_C") (pintype "passive"))
      (node (ref "R15") (pin "1") (pinfunction "1_1") (pintype "passive"))
    )
    (net (code "53") (name "Net-(LED_BAT4-PadC)") (class "Default")
      (node (ref "LED_BAT4") (pin "C") (pinfunction "C_C") (pintype "passive"))
      (node (ref "R16") (pin "1") (pinfunction "1_1") (pintype "passive"))
    )
    (net (code "54") (name "Net-(LED_BAT5-PadC)") (class "Default")
      (node (ref "LED_BAT5") (pin "C") (pinfunction "C_C") (pintype "passive"))
      (node (ref "R17") (pin "1") (pinfunction "1_1") (pintype "passive"))
    )
    (net (code "55") (name "Net-(LED_CONN-PadC)") (class "Default")
      (node (ref "LED_CONN") (pin "C") (pinfunction "C_C") (pintype "passive"))
      (node (ref "R34") (pin "1") (pinfunction "1_1") (pintype "passive"))
    )
    (net (code "56") (name "Net-(LED_KEY-PadC)") (class "Default")
      (node (ref "LED_KEY") (pin "C") (pinfunction "C_C") (pintype "passive"))
      (node (ref "R40") (pin "2") (pinfunction "2_2") (pintype "passive"))
    )
    (net (code "57") (name "Net-(LED_LEG1-PadC)") (class "Default")
      (node (ref "LED_LEG1") (pin "C") (pinfunction "C_C") (pintype "passive"))
      (node (ref "R18") (pin "1") (pinfunction "1_1") (pintype "passive"))
    )
    (net (code "58") (name "Net-(LED_LEG2-PadC)") (class "Default")
      (node (ref "LED_LEG2") (pin "C") (pinfunction "C_C") (pintype "passive"))
      (node (ref "R19") (pin "1") (pinfunction "1_1") (pintype "passive"))
    )
    (net (code "59") (name "Net-(LED_LEG3-PadC)") (class "Default")
      (node (ref "LED_LEG3") (pin "C") (pinfunction "C_C") (pintype "passive"))
      (node (ref "R20") (pin "1") (pinfunction "1_1") (pintype "passive"))
    )
    (net (code "60") (name "Net-(LED_LEG4-PadC)") (class "Default")
      (node (ref "LED_LEG4") (pin "C") (pinfunction "C_C") (pintype "passive"))
      (node (ref "R21") (pin "1") (pinfunction "1_1") (pintype "passive"))
    )
    (net (code "61") (name "Net-(LED_LEG5-PadC)") (class "Default")
      (node (ref "LED_LEG5") (pin "C") (pinfunction "C_C") (pintype "passive"))
      (node (ref "R22") (pin "1") (pinfunction "1_1") (pintype "passive"))
    )
    (net (code "62") (name "Net-(LED_LEG6-PadC)") (class "Default")
      (node (ref "LED_LEG6") (pin "C") (pinfunction "C_C") (pintype "passive"))
      (node (ref "R23") (pin "1") (pinfunction "1_1") (pintype "passive"))
    )
    (net (code "63") (name "Net-(LED_MODE-PadC)") (class "Default")
      (node (ref "LED_MODE") (pin "C") (pinfunction "C_C") (pintype "passive"))
      (node (ref "R39") (pin "1") (pinfunction "1_1") (pintype "passive"))
    )
    (net (code "64") (name "Net-(Q2-S)") (class "Default")
      (node (ref "Q2") (pin "2") (pinfunction "S_2") (pintype "passive"))
      (node (ref "R2") (pin "2") (pinfunction "2_2") (pintype "passive"))
    )
    (net (code "65") (name "Net-(Q3-S)") (class "Default")
      (node (ref "Q3") (pin "2") (pinfunction "S_2") (pintype "passive"))
      (node (ref "R3") (pin "2") (pinfunction "2_2") (pintype "passive"))
    )
    (net (code "66") (name "Net-(Q4-S)") (class "Default")
      (node (ref "Q4") (pin "2") (pinfunction "S_2") (pintype "passive"))
      (node (ref "R4") (pin "2") (pinfunction "2_2") (pintype "passive"))
    )
    (net (code "67") (name "Net-(Q5-S)") (class "Default")
      (node (ref "Q5") (pin "2") (pinfunction "S_2") (pintype "passive"))
      (node (ref "R7") (pin "2") (pinfunction "2_2") (pintype "passive"))
    )
    (net (code "68") (name "Net-(Q6-S)") (class "Default")
      (node (ref "Q6") (pin "2") (pinfunction "S_2") (pintype "passive"))
      (node (ref "R8") (pin "2") (pinfunction "2_2") (pintype "passive"))
    )
    (net (code "69") (name "Net-(Q7-S)") (class "Default")
      (node (ref "Q7") (pin "2") (pinfunction "S_2") (pintype "passive"))
      (node (ref "R11") (pin "2") (pinfunction "2_2") (pintype "passive"))
    )
    (net (code "70") (name "Net-(Q8-S)") (class "Default")
      (node (ref "Q8") (pin "2") (pinfunction "S_2") (pintype "passive"))
      (node (ref "R12") (pin "2") (pinfunction "2_2") (pintype "passive"))
    )
    (net (code "71") (name "Net-(Q10-G)") (class "Default")
      (node (ref "Q10") (pin "1") (pinfunction "G_1") (pintype "passive"))
      (node (ref "R38") (pin "1") (pinfunction "1_1") (pintype "passive"))
    )
    (net (code "72") (name "Net-(Q14-S)") (class "Default")
      (node (ref "Q14") (pin "2") (pinfunction "S_2") (pintype "passive"))
      (node (ref "R1") (pin "2") (pinfunction "2_2") (pintype "passive"))
    )
    (net (code "73") (name "Net-(Q15-S)") (class "Default")
      (node (ref "Q15") (pin "2") (pinfunction "S_2") (pintype "passive"))
      (node (ref "R5") (pin "2") (pinfunction "2_2") (pintype "passive"))
    )
    (net (code "74") (name "Net-(Q17-S)") (class "Default")
      (node (ref "Q17") (pin "2") (pinfunction "S_2") (pintype "passive"))
      (node (ref "R6") (pin "2") (pinfunction "2_2") (pintype "passive"))
    )
    (net (code "75") (name "Net-(Q18-S)") (class "Default")
      (node (ref "Q18") (pin "2") (pinfunction "S_2") (pintype "passive"))
      (node (ref "R9") (pin "2") (pinfunction "2_2") (pintype "passive"))
    )
    (net (code "76") (name "Net-(Q19-S)") (class "Default")
      (node (ref "Q19") (pin "2") (pinfunction "S_2") (pintype "passive"))
      (node (ref "R10") (pin "2") (pinfunction "2_2") (pintype "passive"))
    )
    (net (code "77") (name "Net-(R25-Pad1)") (class "Default")
      (node (ref "R25") (pin "1") (pinfunction "1_1") (pintype "passive"))
      (node (ref "R37") (pin "2") (pinfunction "2_2") (pintype "passive"))
    )
    (net (code "78") (name "Net-(R26-Pad2)") (class "Default")
      (node (ref "R26") (pin "2") (pinfunction "2_2") (pintype "passive"))
      (node (ref "SV13") (pin "17") (pinfunction "17_17") (pintype "passive"))
    )
    (net (code "79") (name "Net-(R27-Pad2)") (class "Default")
      (node (ref "R27") (pin "2") (pinfunction "2_2") (pintype "passive"))
      (node (ref "SV13") (pin "11") (pinfunction "11_11") (pintype "passive"))
    )
    (net (code "80") (name "Net-(R28-Pad2)") (class "Default")
      (node (ref "R28") (pin "2") (pinfunction "2_2") (pintype "passive"))
      (node (ref "SV13") (pin "19") (pinfunction "19_19") (pintype "passive"))
    )
    (net (code "81") (name "Net-(S3.3VB-S)") (class "Default")
      (node (ref "R35") (pin "2") (pinfunction "2_2") (pintype "passive"))
      (node (ref "S3.3V") (pin "4") (pinfunction "S_4") (pintype "passive"))
    )
    (net (code "82") (name "Net-(S5VB-S)") (class "Default")
      (node (ref "R36") (pin "2") (pinfunction "2_2") (pintype "passive"))
      (node (ref "S5V") (pin "4") (pinfunction "S_4") (pintype "passive"))
    )
    (net (code "83") (name "Net-(SKEYBTB-S)") (class "Default")
      (node (ref "LED_KEY") (pin "A") (pinfunction "A_A") (pintype "passive"))
      (node (ref "SKEYBT") (pin "4") (pinfunction "S_4") (pintype "passive"))
    )
    (net (code "84") (name "Net-(X1B-KL)") (class "Default")
      (node (ref "BATTERY") (pin "2") (pinfunction "2_2") (pintype "passive"))
      (node (ref "DC") (pin "2") (pinfunction "2_2") (pintype "passive"))
      (node (ref "F3") (pin "1") (pinfunction "1_1") (pintype "passive"))
      (node (ref "U$1") (pin "P$POS") (pinfunction "P$POS_P$POS") (pintype "bidirectional"))
      (node (ref "X1") (pin "2") (pinfunction "KL_2") (pintype "passive"))
    )
    (net (code "85") (name "RST") (class "Default")
      (node (ref "C9") (pin "2") (pinfunction "2_2") (pintype "passive"))
      (node (ref "IC1") (pin "7") (pinfunction "NRST_7") (pintype "input"))
      (node (ref "S5") (pin "2") (pinfunction "2_2") (pintype "passive"))
      (node (ref "SV13") (pin "15") (pinfunction "15_15") (pintype "passive"))
    )
    (net (code "86") (name "SERWO1") (class "Default")
      (node (ref "IC1") (pin "18") (pinfunction "PB0_18") (pintype "bidirectional"))
      (node (ref "Q14") (pin "3") (pinfunction "G_3") (pintype "passive"))
    )
    (net (code "87") (name "SERWO2") (class "Default")
      (node (ref "IC1") (pin "19") (pinfunction "PB1_19") (pintype "bidirectional"))
      (node (ref "Q2") (pin "3") (pinfunction "G_3") (pintype "passive"))
    )
    (net (code "88") (name "SERWO3") (class "Default")
      (node (ref "IC1") (pin "20") (pinfunction "PB2_20") (pintype "bidirectional"))
      (node (ref "Q15") (pin "3") (pinfunction "G_3") (pintype "passive"))
    )
    (net (code "89") (name "SERWO4") (class "Default")
      (node (ref "IC1") (pin "41") (pinfunction "PB5_41") (pintype "bidirectional"))
      (node (ref "Q17") (pin "3") (pinfunction "G_3") (pintype "passive"))
    )
    (net (code "90") (name "SERWO5") (class "Default")
      (node (ref "IC1") (pin "42") (pinfunction "PB6_42") (pintype "bidirectional"))
      (node (ref "Q18") (pin "3") (pinfunction "G_3") (pintype "passive"))
    )
    (net (code "91") (name "SERWO6") (class "Default")
      (node (ref "IC1") (pin "43") (pinfunction "PB7_43") (pintype "bidirectional"))
      (node (ref "Q19") (pin "3") (pinfunction "G_3") (pintype "passive"))
    )
    (net (code "92") (name "SERWO7") (class "Default")
      (node (ref "IC1") (pin "45") (pinfunction "PB8_45") (pintype "bidirectional"))
      (node (ref "Q3") (pin "3") (pinfunction "G_3") (pintype "passive"))
    )
    (net (code "93") (name "SERWO8") (class "Default")
      (node (ref "IC1") (pin "46") (pinfunction "PB9_46") (pintype "bidirectional"))
      (node (ref "Q4") (pin "3") (pinfunction "G_3") (pintype "passive"))
    )
    (net (code "94") (name "SERWO9") (class "Default")
      (node (ref "IC1") (pin "25") (pinfunction "PB12_25") (pintype "bidirectional"))
      (node (ref "Q5") (pin "3") (pinfunction "G_3") (pintype "passive"))
    )
    (net (code "95") (name "SERWO10") (class "Default")
      (node (ref "IC1") (pin "26") (pinfunction "PB13_26") (pintype "bidirectional"))
      (node (ref "Q6") (pin "3") (pinfunction "G_3") (pintype "passive"))
    )
    (net (code "96") (name "SERWO11") (class "Default")
      (node (ref "IC1") (pin "27") (pinfunction "PB14_27") (pintype "bidirectional"))
      (node (ref "Q7") (pin "3") (pinfunction "G_3") (pintype "passive"))
    )
    (net (code "97") (name "SERWO12") (class "Default")
      (node (ref "IC1") (pin "28") (pinfunction "PB15_28") (pintype "bidirectional"))
      (node (ref "Q8") (pin "3") (pinfunction "G_3") (pintype "passive"))
    )
    (net (code "98") (name "USART_RX") (class "Default")
      (node (ref "IC1") (pin "21") (pinfunction "PB10_21") (pintype "bidirectional"))
      (node (ref "U1") (pin "2") (pinfunction "RX_2") (pintype "bidirectional"))
    )
    (net (code "99") (name "USART_TX") (class "Default")
      (node (ref "IC1") (pin "22") (pinfunction "PB11_22") (pintype "bidirectional"))
      (node (ref "U1") (pin "1") (pinfunction "TX_1") (pintype "bidirectional"))
    )
    (net (code "100") (name "unconnected-(DC-Pad3)") (class "Default")
      (node (ref "DC") (pin "3") (pinfunction "3_3") (pintype "passive"))
    )
    (net (code "101") (name "unconnected-(IC1C-PA7-Pad17)") (class "Default")
      (node (ref "IC1") (pin "17") (pinfunction "PA7_17") (pintype "bidirectional"))
    )
    (net (code "102") (name "unconnected-(IC1F-PC14-Pad3)") (class "Default")
      (node (ref "IC1") (pin "3") (pinfunction "PC14_3") (pintype "bidirectional"))
    )
    (net (code "103") (name "unconnected-(IC1F-PC15-Pad4)") (class "Default")
      (node (ref "IC1") (pin "4") (pinfunction "PC15_4") (pintype "bidirectional"))
    )
    (net (code "104") (name "unconnected-(IC1I-BOOT0-Pad44)") (class "Default")
      (node (ref "IC1") (pin "44") (pinfunction "BOOT0_44") (pintype "input"))
    )
    (net (code "105") (name "unconnected-(S3.3VA-O-Pad3)") (class "Default")
      (node (ref "S3.3V") (pin "3") (pinfunction "O_3") (pintype "passive"))
    )
    (net (code "106") (name "unconnected-(S3.3VB-O-Pad6)") (class "Default")
      (node (ref "S3.3V") (pin "6") (pinfunction "O_6") (pintype "passive"))
    )
    (net (code "107") (name "unconnected-(S5VA-O-Pad3)") (class "Default")
      (node (ref "S5V") (pin "3") (pinfunction "O_3") (pintype "passive"))
    )
    (net (code "108") (name "unconnected-(S5VB-O-Pad6)") (class "Default")
      (node (ref "S5V") (pin "6") (pinfunction "O_6") (pintype "passive"))
    )
    (net (code "109") (name "unconnected-(SKEYBTB-O-Pad6)") (class "Default")
      (node (ref "SKEYBT") (pin "6") (pinfunction "O_6") (pintype "passive"))
    )
    (net (code "110") (name "unconnected-(U1-AIO0-Pad9)") (class "Default")
      (node (ref "U1") (pin "9") (pinfunction "AIO0_9") (pintype "bidirectional"))
    )
    (net (code "111") (name "unconnected-(U1-AIO1-Pad10)") (class "Default")
      (node (ref "U1") (pin "10") (pinfunction "AIO1_10") (pintype "bidirectional"))
    )
    (net (code "112") (name "unconnected-(U1-CLK-Pad19)") (class "Default")
      (node (ref "U1") (pin "19") (pinfunction "CLK_19") (pintype "bidirectional"))
    )
    (net (code "113") (name "unconnected-(U1-CSB-Pad16)") (class "Default")
      (node (ref "U1") (pin "16") (pinfunction "CSB_16") (pintype "bidirectional"))
    )
    (net (code "114") (name "unconnected-(U1-CTS-Pad3)") (class "Default")
      (node (ref "U1") (pin "3") (pinfunction "CTS_3") (pintype "bidirectional"))
    )
    (net (code "115") (name "unconnected-(U1-MISO-Pad18)") (class "Default")
      (node (ref "U1") (pin "18") (pinfunction "MISO_18") (pintype "bidirectional"))
    )
    (net (code "116") (name "unconnected-(U1-MOSI-Pad17)") (class "Default")
      (node (ref "U1") (pin "17") (pinfunction "MOSI_17") (pintype "bidirectional"))
    )
    (net (code "117") (name "unconnected-(U1-NC-Pad14)") (class "Default")
      (node (ref "U1") (pin "14") (pinfunction "NC_14") (pintype "bidirectional"))
    )
    (net (code "118") (name "unconnected-(U1-PCM_CLK-Pad5)") (class "Default")
      (node (ref "U1") (pin "5") (pinfunction "PCM_CLK_5") (pintype "bidirectional"))
    )
    (net (code "119") (name "unconnected-(U1-PCM_IN-Pad7)") (class "Default")
      (node (ref "U1") (pin "7") (pinfunction "PCM_IN_7") (pintype "bidirectional"))
    )
    (net (code "120") (name "unconnected-(U1-PCM_OUT-Pad6)") (class "Default")
      (node (ref "U1") (pin "6") (pinfunction "PCM_OUT_6") (pintype "bidirectional"))
    )
    (net (code "121") (name "unconnected-(U1-PCN_SYNC-Pad8)") (class "Default")
      (node (ref "U1") (pin "8") (pinfunction "PCN_SYNC_8") (pintype "bidirectional"))
    )
    (net (code "122") (name "unconnected-(U1-PIO0-Pad23)") (class "Default")
      (node (ref "U1") (pin "23") (pinfunction "PIO0_23") (pintype "bidirectional"))
    )
    (net (code "123") (name "unconnected-(U1-PIO1-Pad24)") (class "Default")
      (node (ref "U1") (pin "24") (pinfunction "PIO1_24") (pintype "bidirectional"))
    )
    (net (code "124") (name "unconnected-(U1-PIO2-Pad25)") (class "Default")
      (node (ref "U1") (pin "25") (pinfunction "PIO2_25") (pintype "bidirectional"))
    )
    (net (code "125") (name "unconnected-(U1-PIO3-Pad26)") (class "Default")
      (node (ref "U1") (pin "26") (pinfunction "PIO3_26") (pintype "bidirectional"))
    )
    (net (code "126") (name "unconnected-(U1-PIO4-Pad27)") (class "Default")
      (node (ref "U1") (pin "27") (pinfunction "PIO4_27") (pintype "bidirectional"))
    )
    (net (code "127") (name "unconnected-(U1-PIO5-Pad28)") (class "Default")
      (node (ref "U1") (pin "28") (pinfunction "PIO5_28") (pintype "bidirectional"))
    )
    (net (code "128") (name "unconnected-(U1-PIO6-Pad29)") (class "Default")
      (node (ref "U1") (pin "29") (pinfunction "PIO6_29") (pintype "bidirectional"))
    )
    (net (code "129") (name "unconnected-(U1-PIO7-Pad30)") (class "Default")
      (node (ref "U1") (pin "30") (pinfunction "PIO7_30") (pintype "bidirectional"))
    )
    (net (code "130") (name "unconnected-(U1-PIO10-Pad33)") (class "Default")
      (node (ref "U1") (pin "33") (pinfunction "PIO10_33") (pintype "bidirectional"))
    )
    (net (code "131") (name "unconnected-(U1-RST-Pad11)") (class "Default")
      (node (ref "U1") (pin "11") (pinfunction "RST_11") (pintype "bidirectional"))
    )
    (net (code "132") (name "unconnected-(U1-RTS-Pad4)") (class "Default")
      (node (ref "U1") (pin "4") (pinfunction "RTS_4") (pintype "bidirectional"))
    )
    (net (code "133") (name "unconnected-(U1-VBUSD+-Pad20)") (class "Default")
      (node (ref "U1") (pin "20") (pinfunction "VBUSD+_20") (pintype "bidirectional"))
    )
    (net (code "134") (name "unconnected-(U1-VBUSD--Pad15)") (class "Default")
      (node (ref "U1") (pin "15") (pinfunction "VBUSD-_15") (pintype "bidirectional"))
    )
  )
)
